# Top.net
KiCad netlist of a schematic drawn in Altium Designer
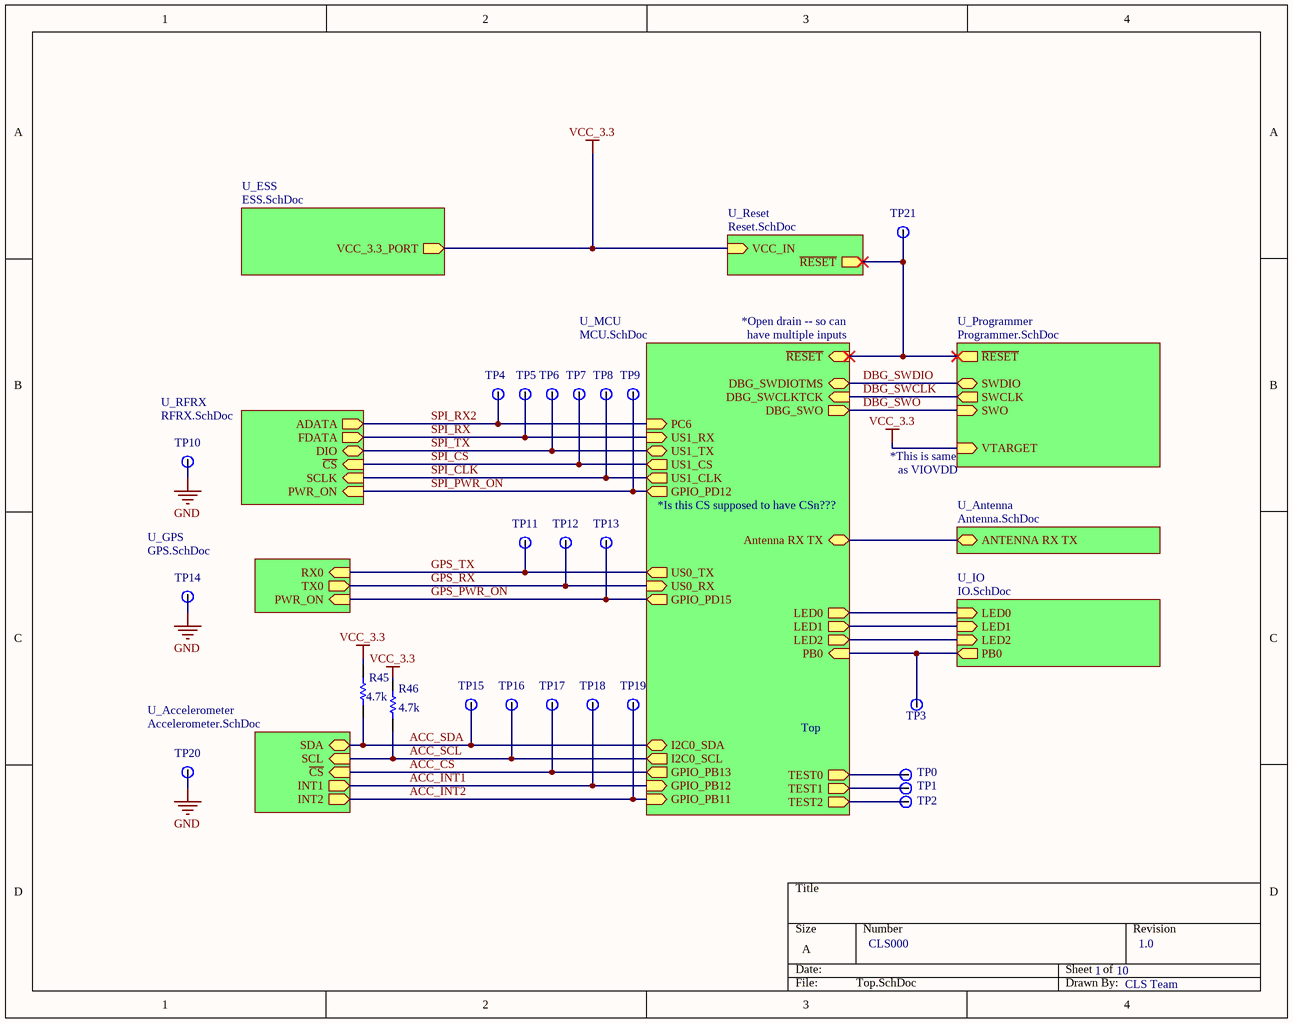
[diagram p0: Top.SchDoc]

(export (version "E")
  (design (tool "Eeschema 10.0.6"))
  (components
    (comp (ref "R45")
      (value "4.7k")
      (footprint "0805_CHIP_FP")
      (description "Resistor 0805")
      (fields
        (field (name "MANUFACTURER") "Yageo")
        (field (name "MANUFACTURER PART NUMBER") "RC0805JR-074K7L")
      )
      (libsource (lib "GenericSymbols") (part "Resistor_0805"))
    )
    (comp (ref "R46")
      (value "4.7k")
      (footprint "0805_CHIP_FP")
      (description "Resistor 0805")
      (fields
        (field (name "MANUFACTURER") "Yageo")
        (field (name "MANUFACTURER PART NUMBER") "RC0805JR-074K7L")
      )
      (libsource (lib "GenericSymbols") (part "Resistor_0805"))
    )
    (comp (ref "TP0")
      (value "Testpoint")
      (footprint "HDR1X1")
      (fields (field (name "MANUFACTURER") "Sparkfun") (field (name "VENDOR PART NUMBER") "PRT-00116"))
      (libsource (lib "Testpoint") (part "Testpoint"))
    )
    (comp (ref "TP1")
      (value "Testpoint")
      (footprint "HDR1X1")
      (fields (field (name "MANUFACTURER") "Sparkfun") (field (name "VENDOR PART NUMBER") "PRT-00116"))
      (libsource (lib "Testpoint") (part "Testpoint"))
    )
    (comp (ref "TP2")
      (value "Testpoint")
      (footprint "HDR1X1")
      (fields (field (name "MANUFACTURER") "Sparkfun") (field (name "VENDOR PART NUMBER") "PRT-00116"))
      (libsource (lib "Testpoint") (part "Testpoint"))
    )
    (comp (ref "TP3")
      (value "Testpoint")
      (footprint "HDR1X1")
      (fields (field (name "MANUFACTURER") "Sparkfun") (field (name "VENDOR PART NUMBER") "PRT-00116"))
      (libsource (lib "Testpoint") (part "Testpoint"))
    )
    (comp (ref "TP4")
      (value "Testpoint")
      (footprint "HDR1X1")
      (fields (field (name "MANUFACTURER") "Sparkfun") (field (name "VENDOR PART NUMBER") "PRT-00116"))
      (libsource (lib "Testpoint") (part "Testpoint"))
    )
    (comp (ref "TP5")
      (value "Testpoint")
      (footprint "HDR1X1")
      (fields (field (name "MANUFACTURER") "Sparkfun") (field (name "VENDOR PART NUMBER") "PRT-00116"))
      (libsource (lib "Testpoint") (part "Testpoint"))
    )
    (comp (ref "TP6")
      (value "Testpoint")
      (footprint "HDR1X1")
      (fields (field (name "MANUFACTURER") "Sparkfun") (field (name "VENDOR PART NUMBER") "PRT-00116"))
      (libsource (lib "Testpoint") (part "Testpoint"))
    )
    (comp (ref "TP7")
      (value "Testpoint")
      (footprint "HDR1X1")
      (fields (field (name "MANUFACTURER") "Sparkfun") (field (name "VENDOR PART NUMBER") "PRT-00116"))
      (libsource (lib "Testpoint") (part "Testpoint"))
    )
    (comp (ref "TP8")
      (value "Testpoint")
      (footprint "HDR1X1")
      (fields (field (name "MANUFACTURER") "Sparkfun") (field (name "VENDOR PART NUMBER") "PRT-00116"))
      (libsource (lib "Testpoint") (part "Testpoint"))
    )
    (comp (ref "TP9")
      (value "Testpoint")
      (footprint "HDR1X1")
      (fields (field (name "MANUFACTURER") "Sparkfun") (field (name "VENDOR PART NUMBER") "PRT-00116"))
      (libsource (lib "Testpoint") (part "Testpoint"))
    )
    (comp (ref "TP10")
      (value "Testpoint")
      (footprint "HDR1X1")
      (fields (field (name "MANUFACTURER") "Sparkfun") (field (name "VENDOR PART NUMBER") "PRT-00116"))
      (libsource (lib "Testpoint") (part "Testpoint"))
    )
    (comp (ref "TP11")
      (value "Testpoint")
      (footprint "HDR1X1")
      (fields (field (name "MANUFACTURER") "Sparkfun") (field (name "VENDOR PART NUMBER") "PRT-00116"))
      (libsource (lib "Testpoint") (part "Testpoint"))
    )
    (comp (ref "TP12")
      (value "Testpoint")
      (footprint "HDR1X1")
      (fields (field (name "MANUFACTURER") "Sparkfun") (field (name "VENDOR PART NUMBER") "PRT-00116"))
      (libsource (lib "Testpoint") (part "Testpoint"))
    )
    (comp (ref "TP13")
      (value "Testpoint")
      (footprint "HDR1X1")
      (fields (field (name "MANUFACTURER") "Sparkfun") (field (name "VENDOR PART NUMBER") "PRT-00116"))
      (libsource (lib "Testpoint") (part "Testpoint"))
    )
    (comp (ref "TP14")
      (value "Testpoint")
      (footprint "HDR1X1")
      (fields (field (name "MANUFACTURER") "Sparkfun") (field (name "VENDOR PART NUMBER") "PRT-00116"))
      (libsource (lib "Testpoint") (part "Testpoint"))
    )
    (comp (ref "TP15")
      (value "Testpoint")
      (footprint "HDR1X1")
      (fields (field (name "MANUFACTURER") "Sparkfun") (field (name "VENDOR PART NUMBER") "PRT-00116"))
      (libsource (lib "Testpoint") (part "Testpoint"))
    )
    (comp (ref "TP16")
      (value "Testpoint")
      (footprint "HDR1X1")
      (fields (field (name "MANUFACTURER") "Sparkfun") (field (name "VENDOR PART NUMBER") "PRT-00116"))
      (libsource (lib "Testpoint") (part "Testpoint"))
    )
    (comp (ref "TP17")
      (value "Testpoint")
      (footprint "HDR1X1")
      (fields (field (name "MANUFACTURER") "Sparkfun") (field (name "VENDOR PART NUMBER") "PRT-00116"))
      (libsource (lib "Testpoint") (part "Testpoint"))
    )
    (comp (ref "TP18")
      (value "Testpoint")
      (footprint "HDR1X1")
      (fields (field (name "MANUFACTURER") "Sparkfun") (field (name "VENDOR PART NUMBER") "PRT-00116"))
      (libsource (lib "Testpoint") (part "Testpoint"))
    )
    (comp (ref "TP19")
      (value "Testpoint")
      (footprint "HDR1X1")
      (fields (field (name "MANUFACTURER") "Sparkfun") (field (name "VENDOR PART NUMBER") "PRT-00116"))
      (libsource (lib "Testpoint") (part "Testpoint"))
    )
    (comp (ref "TP20")
      (value "Testpoint")
      (footprint "HDR1X1")
      (fields (field (name "MANUFACTURER") "Sparkfun") (field (name "VENDOR PART NUMBER") "PRT-00116"))
      (libsource (lib "Testpoint") (part "Testpoint"))
    )
    (comp (ref "TP21")
      (value "Testpoint")
      (footprint "HDR1X1")
      (fields (field (name "MANUFACTURER") "Sparkfun") (field (name "VENDOR PART NUMBER") "PRT-00116"))
      (libsource (lib "Testpoint") (part "Testpoint"))
    )
  )
  (nets
    (net (code "1") (name "/ACC_INT1") (class "Default")
      (node (ref "TP18") (pin "1") (pinfunction "OUT_1") (pintype "input"))
    )
    (net (code "2") (name "/ACC_INT2") (class "Default")
      (node (ref "TP19") (pin "1") (pinfunction "OUT_1") (pintype "input"))
    )
    (net (code "3") (name "/ACC_SCL") (class "Default")
      (node (ref "R46") (pin "1") (pinfunction "1_1") (pintype "passive"))
      (node (ref "TP16") (pin "1") (pinfunction "OUT_1") (pintype "input"))
    )
    (net (code "4") (name "/ACC_SDA") (class "Default")
      (node (ref "R45") (pin "1") (pinfunction "1_1") (pintype "passive"))
      (node (ref "TP15") (pin "1") (pinfunction "OUT_1") (pintype "input"))
    )
    (net (code "5") (name "/ACC_~{CS}") (class "Default")
      (node (ref "TP17") (pin "1") (pinfunction "OUT_1") (pintype "input"))
    )
    (net (code "10") (name "/GPS_PWR_ON") (class "Default")
      (node (ref "TP13") (pin "1") (pinfunction "OUT_1") (pintype "input"))
    )
    (net (code "11") (name "/GPS_RX") (class "Default")
      (node (ref "TP12") (pin "1") (pinfunction "OUT_1") (pintype "input"))
    )
    (net (code "12") (name "/GPS_TX") (class "Default")
      (node (ref "TP11") (pin "1") (pinfunction "OUT_1") (pintype "input"))
    )
    (net (code "16") (name "/PB0") (class "Default")
      (node (ref "TP3") (pin "1") (pinfunction "OUT_1") (pintype "input"))
    )
    (net (code "17") (name "/SPI_CLK") (class "Default")
      (node (ref "TP8") (pin "1") (pinfunction "OUT_1") (pintype "input"))
    )
    (net (code "18") (name "/SPI_PWR_ON") (class "Default")
      (node (ref "TP9") (pin "1") (pinfunction "OUT_1") (pintype "input"))
    )
    (net (code "19") (name "/SPI_RX") (class "Default")
      (node (ref "TP5") (pin "1") (pinfunction "OUT_1") (pintype "input"))
    )
    (net (code "20") (name "/SPI_RX2") (class "Default")
      (node (ref "TP4") (pin "1") (pinfunction "OUT_1") (pintype "input"))
    )
    (net (code "21") (name "/SPI_TX") (class "Default")
      (node (ref "TP6") (pin "1") (pinfunction "OUT_1") (pintype "input"))
    )
    (net (code "22") (name "/SPI_~{CS}") (class "Default")
      (node (ref "TP7") (pin "1") (pinfunction "OUT_1") (pintype "input"))
    )
    (net (code "23") (name "/TEST0") (class "Default")
      (node (ref "TP0") (pin "1") (pinfunction "OUT_1") (pintype "input"))
    )
    (net (code "24") (name "/TEST1") (class "Default")
      (node (ref "TP1") (pin "1") (pinfunction "OUT_1") (pintype "input"))
    )
    (net (code "25") (name "/TEST2") (class "Default")
      (node (ref "TP2") (pin "1") (pinfunction "OUT_1") (pintype "input"))
    )
    (net (code "26") (name "/~{RESET}") (class "Default")
      (node (ref "TP21") (pin "1") (pinfunction "OUT_1") (pintype "input+no_connect"))
    )
    (net (code "27") (name "GND") (class "Default")
      (node (ref "TP10") (pin "1") (pinfunction "OUT_1") (pintype "input"))
      (node (ref "TP14") (pin "1") (pinfunction "OUT_1") (pintype "input"))
      (node (ref "TP20") (pin "1") (pinfunction "OUT_1") (pintype "input"))
    )
    (net (code "28") (name "VCC_3.3") (class "Default")
      (node (ref "R45") (pin "2") (pinfunction "2_2") (pintype "passive"))
      (node (ref "R46") (pin "2") (pinfunction "2_2") (pintype "passive"))
    )
  )
)
